# MS20_Filter_clone.net
KiCad netlist of a schematic drawn in EAGLE
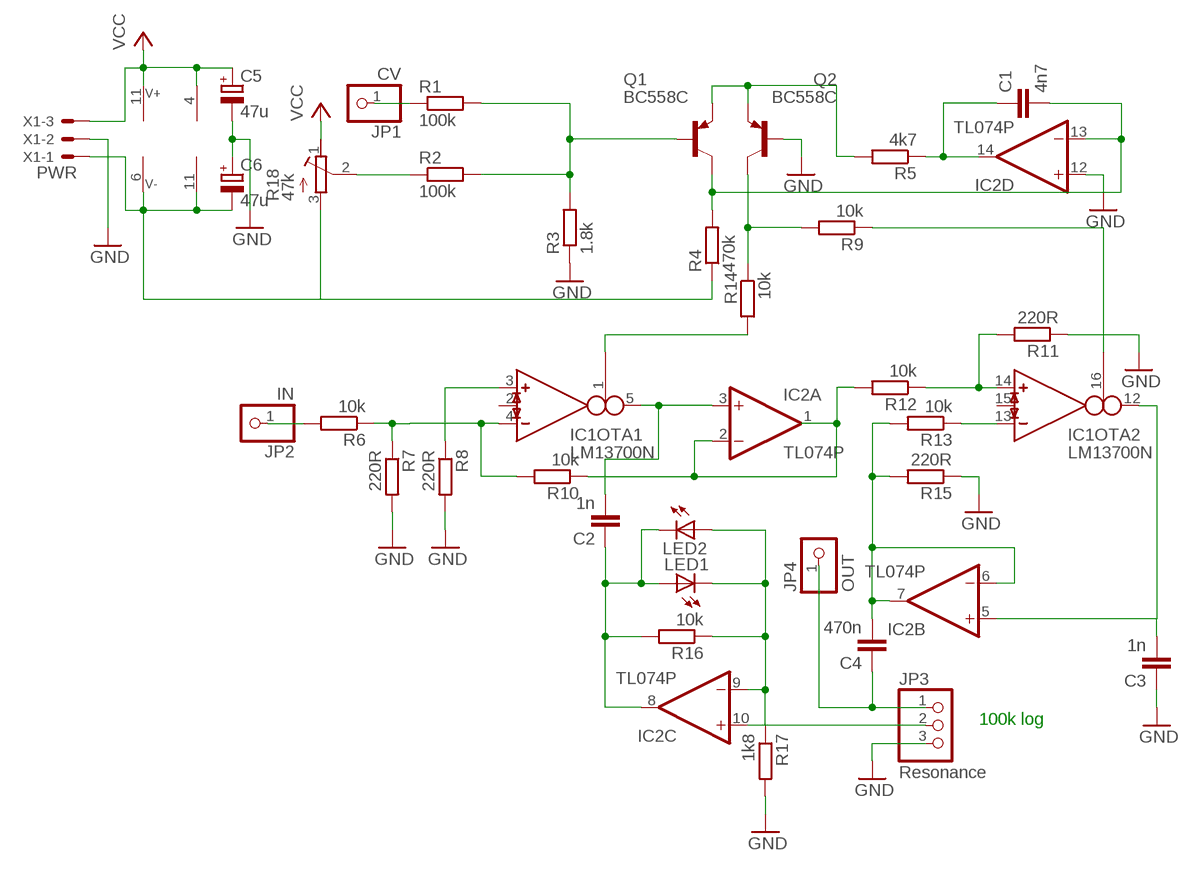
[diagram p0: schematic, sheet 1]

(export (version "E")
  (design (tool "Eeschema 10.0.6"))
  (components
    (comp (ref "C1")
      (value "4n7")
      (footprint "eagle-import:C050-024X044")
      (libsource (lib "eagle-import") (part "C-EU050-024X044"))
    )
    (comp (ref "C2")
      (value "1n")
      (footprint "eagle-import:C050-024X044")
      (libsource (lib "eagle-import") (part "C-EU050-024X044"))
    )
    (comp (ref "C3")
      (value "1n")
      (footprint "eagle-import:C050-024X044")
      (libsource (lib "eagle-import") (part "C-EU050-024X044"))
    )
    (comp (ref "C4")
      (value "470n")
      (footprint "eagle-import:C050-024X044")
      (libsource (lib "eagle-import") (part "C-EU050-024X044"))
    )
    (comp (ref "C5")
      (value "47u")
      (footprint "eagle-import:E2,5-6")
      (libsource (lib "eagle-import") (part "CPOL-EUE2.5-6"))
    )
    (comp (ref "C6")
      (value "47u")
      (footprint "eagle-import:E2,5-6")
      (libsource (lib "eagle-import") (part "CPOL-EUE2.5-6"))
    )
    (comp (ref "IC1")
      (value "LM13700N")
      (footprint "eagle-import:DIL16")
      (libsource (lib "eagle-import") (part "LM13700N"))
    )
    (comp (ref "IC2")
      (value "TL074P")
      (footprint "eagle-import:DIL14")
      (libsource (lib "eagle-import") (part "TL074P"))
    )
    (comp (ref "JP1")
      (value "CV")
      (footprint "eagle-import:1X01")
      (libsource (lib "eagle-import") (part "PINHD-1X1"))
    )
    (comp (ref "JP2")
      (value "IN")
      (footprint "eagle-import:1X01")
      (libsource (lib "eagle-import") (part "PINHD-1X1"))
    )
    (comp (ref "JP3")
      (value "Resonance")
      (footprint "eagle-import:1X03-CLEANBIG")
      (libsource (lib "eagle-import") (part "PINHD-1X3CB"))
    )
    (comp (ref "JP4")
      (value "OUT")
      (footprint "eagle-import:1X01")
      (libsource (lib "eagle-import") (part "PINHD-1X1"))
    )
    (comp (ref "LED1")
      (value "LED5MM")
      (footprint "eagle-import:LED5MM")
      (libsource (lib "eagle-import") (part "LED5MM"))
    )
    (comp (ref "LED2")
      (value "LED5MM")
      (footprint "eagle-import:LED5MM")
      (libsource (lib "eagle-import") (part "LED5MM"))
    )
    (comp (ref "Q1")
      (value "BC558C")
      (footprint "eagle-import:TO92-EBC")
      (libsource (lib "eagle-import") (part "BC558C"))
    )
    (comp (ref "Q2")
      (value "BC558C")
      (footprint "eagle-import:TO92-EBC")
      (libsource (lib "eagle-import") (part "BC558C"))
    )
    (comp (ref "R1")
      (value "100k")
      (footprint "eagle-import:0204_5")
      (libsource (lib "eagle-import") (part "R-EU_0204/5"))
    )
    (comp (ref "R2")
      (value "100k")
      (footprint "eagle-import:0204_7")
      (libsource (lib "eagle-import") (part "R-EU_0204/7"))
    )
    (comp (ref "R3")
      (value "1.8k")
      (footprint "eagle-import:0204_7")
      (libsource (lib "eagle-import") (part "R-EU_0204/7"))
    )
    (comp (ref "R4")
      (value "470k")
      (footprint "eagle-import:0204_7")
      (libsource (lib "eagle-import") (part "R-EU_0204/7"))
    )
    (comp (ref "R5")
      (value "4k7")
      (footprint "eagle-import:0204V")
      (libsource (lib "eagle-import") (part "R-EU_0204/2V"))
    )
    (comp (ref "R6")
      (value "10k")
      (footprint "eagle-import:0204_7")
      (libsource (lib "eagle-import") (part "R-EU_0204/7"))
    )
    (comp (ref "R7")
      (value "220R")
      (footprint "eagle-import:0204_7")
      (libsource (lib "eagle-import") (part "R-EU_0204/7"))
    )
    (comp (ref "R8")
      (value "220R")
      (footprint "eagle-import:0204_7")
      (libsource (lib "eagle-import") (part "R-EU_0204/7"))
    )
    (comp (ref "R9")
      (value "10k")
      (footprint "eagle-import:0204_7")
      (libsource (lib "eagle-import") (part "R-EU_0204/7"))
    )
    (comp (ref "R10")
      (value "10k")
      (footprint "eagle-import:0204_5")
      (libsource (lib "eagle-import") (part "R-EU_0204/5"))
    )
    (comp (ref "R11")
      (value "220R")
      (footprint "eagle-import:0204_5")
      (libsource (lib "eagle-import") (part "R-EU_0204/5"))
    )
    (comp (ref "R12")
      (value "10k")
      (footprint "eagle-import:0204_7")
      (libsource (lib "eagle-import") (part "R-EU_0204/7"))
    )
    (comp (ref "R13")
      (value "10k")
      (footprint "eagle-import:0204_5")
      (libsource (lib "eagle-import") (part "R-EU_0204/5"))
    )
    (comp (ref "R14")
      (value "10k")
      (footprint "eagle-import:0204V")
      (libsource (lib "eagle-import") (part "R-EU_0204/2V"))
    )
    (comp (ref "R15")
      (value "220R")
      (footprint "eagle-import:0204V")
      (libsource (lib "eagle-import") (part "R-EU_0204/2V"))
    )
    (comp (ref "R16")
      (value "10k")
      (footprint "eagle-import:0204V")
      (libsource (lib "eagle-import") (part "R-EU_0204/2V"))
    )
    (comp (ref "R17")
      (value "1k8")
      (footprint "eagle-import:0204V")
      (libsource (lib "eagle-import") (part "R-EU_0204/2V"))
    )
    (comp (ref "R18")
      (value "47k")
      (footprint "eagle-import:RTRIMT93YA")
      (libsource (lib "eagle-import") (part "R-TRIMMT93YA"))
    )
    (comp (ref "X1")
      (value "PWR")
      (footprint "eagle-import:JST-XH-03-PACKAGE-LONG-PAD")
      (libsource (lib "eagle-import") (part "JST-XH-03-PIN-LONG-PAD"))
    )
  )
  (nets
    (net (code "1") (name "GND") (class "Default")
      (node (ref "C3") (pin "1") (pinfunction "1_1") (pintype "passive"))
      (node (ref "C5") (pin "-") (pinfunction "-_-") (pintype "passive"))
      (node (ref "C6") (pin "+") (pinfunction "+_+") (pintype "passive"))
      (node (ref "IC2") (pin "12") (pinfunction "+IN_12") (pintype "input"))
      (node (ref "JP3") (pin "3") (pinfunction "3_3") (pintype "passive"))
      (node (ref "Q2") (pin "B") (pinfunction "B_B") (pintype "passive"))
      (node (ref "R11") (pin "1") (pinfunction "1_1") (pintype "passive"))
      (node (ref "R15") (pin "1") (pinfunction "1_1") (pintype "passive"))
      (node (ref "R17") (pin "2") (pinfunction "2_2") (pintype "passive"))
      (node (ref "R3") (pin "1") (pinfunction "1_1") (pintype "passive"))
      (node (ref "R7") (pin "2") (pinfunction "2_2") (pintype "passive"))
      (node (ref "R8") (pin "2") (pinfunction "2_2") (pintype "passive"))
      (node (ref "X1") (pin "2") (pinfunction "S_2") (pintype "passive"))
    )
    (net (code "2") (name "Net-(C4-Pad1)") (class "Default")
      (node (ref "C4") (pin "1") (pinfunction "1_1") (pintype "passive"))
      (node (ref "JP3") (pin "1") (pinfunction "1_1") (pintype "passive"))
      (node (ref "JP4") (pin "1") (pinfunction "1_1") (pintype "passive"))
    )
    (net (code "3") (name "Net-(IC1C-IN_N)") (class "Default")
      (node (ref "IC1") (pin "4") (pinfunction "IN_N_4") (pintype "input"))
      (node (ref "R10") (pin "2") (pinfunction "2_2") (pintype "passive"))
      (node (ref "R6") (pin "1") (pinfunction "1_1") (pintype "passive"))
      (node (ref "R7") (pin "1") (pinfunction "1_1") (pintype "passive"))
    )
    (net (code "4") (name "Net-(IC1C-IN_P)") (class "Default")
      (node (ref "IC1") (pin "3") (pinfunction "IN_P_3") (pintype "input"))
      (node (ref "R8") (pin "1") (pinfunction "1_1") (pintype "passive"))
    )
    (net (code "5") (name "Net-(IC1C-I_BIAS)") (class "Default")
      (node (ref "IC1") (pin "1") (pinfunction "I_BIAS_1") (pintype "input"))
      (node (ref "R14") (pin "2") (pinfunction "2_2") (pintype "passive"))
    )
    (net (code "6") (name "Net-(IC1C-OUT)") (class "Default")
      (node (ref "C2") (pin "2") (pinfunction "2_2") (pintype "passive"))
      (node (ref "IC1") (pin "5") (pinfunction "OUT_5") (pintype "output"))
      (node (ref "IC2") (pin "3") (pinfunction "+IN_3") (pintype "input"))
    )
    (net (code "7") (name "Net-(IC1D-IN_N)") (class "Default")
      (node (ref "IC1") (pin "13") (pinfunction "IN_N_13") (pintype "input"))
      (node (ref "R13") (pin "1") (pinfunction "1_1") (pintype "passive"))
    )
    (net (code "8") (name "Net-(IC1D-IN_P)") (class "Default")
      (node (ref "IC1") (pin "14") (pinfunction "IN_P_14") (pintype "input"))
      (node (ref "R11") (pin "2") (pinfunction "2_2") (pintype "passive"))
      (node (ref "R12") (pin "1") (pinfunction "1_1") (pintype "passive"))
    )
    (net (code "9") (name "Net-(IC1D-I_BIAS)") (class "Default")
      (node (ref "IC1") (pin "16") (pinfunction "I_BIAS_16") (pintype "input"))
      (node (ref "R9") (pin "1") (pinfunction "1_1") (pintype "passive"))
    )
    (net (code "10") (name "Net-(IC1D-OUT)") (class "Default")
      (node (ref "C3") (pin "2") (pinfunction "2_2") (pintype "passive"))
      (node (ref "IC1") (pin "12") (pinfunction "OUT_12") (pintype "output"))
      (node (ref "IC2") (pin "5") (pinfunction "+IN_5") (pintype "input"))
    )
    (net (code "11") (name "Net-(IC1E-V-)") (class "Default")
      (node (ref "C6") (pin "-") (pinfunction "-_-") (pintype "passive"))
      (node (ref "IC1") (pin "6") (pinfunction "V-_6") (pintype "power_in"))
      (node (ref "IC2") (pin "11") (pinfunction "V-_11") (pintype "power_in"))
      (node (ref "R18") (pin "3") (pinfunction "A_3") (pintype "passive"))
      (node (ref "R4") (pin "1") (pinfunction "1_1") (pintype "passive"))
      (node (ref "X1") (pin "1") (pinfunction "S_1") (pintype "passive"))
    )
    (net (code "12") (name "Net-(IC2A--IN)") (class "Default")
      (node (ref "IC2") (pin "2") (pinfunction "-IN_2") (pintype "input"))
      (node (ref "R10") (pin "1") (pinfunction "1_1") (pintype "passive"))
      (node (ref "R12") (pin "2") (pinfunction "2_2") (pintype "passive"))
    )
    (net (code "13") (name "Net-(IC2B--IN)") (class "Default")
      (node (ref "C4") (pin "2") (pinfunction "2_2") (pintype "passive"))
      (node (ref "IC2") (pin "6") (pinfunction "-IN_6") (pintype "input"))
      (node (ref "IC2") (pin "7") (pinfunction "OUT_7") (pintype "output"))
      (node (ref "R13") (pin "2") (pinfunction "2_2") (pintype "passive"))
      (node (ref "R15") (pin "2") (pinfunction "2_2") (pintype "passive"))
    )
    (net (code "14") (name "Net-(IC2C-+IN)") (class "Default")
      (node (ref "IC2") (pin "10") (pinfunction "+IN_10") (pintype "input"))
      (node (ref "JP3") (pin "2") (pinfunction "2_2") (pintype "passive"))
    )
    (net (code "15") (name "Net-(IC2C--IN)") (class "Default")
      (node (ref "IC2") (pin "9") (pinfunction "-IN_9") (pintype "input"))
      (node (ref "LED1") (pin "K") (pinfunction "C_K") (pintype "passive"))
      (node (ref "LED2") (pin "A") (pinfunction "A_A") (pintype "passive"))
      (node (ref "R16") (pin "1") (pinfunction "1_1") (pintype "passive"))
      (node (ref "R17") (pin "1") (pinfunction "1_1") (pintype "passive"))
    )
    (net (code "16") (name "Net-(IC2C-OUT)") (class "Default")
      (node (ref "C2") (pin "1") (pinfunction "1_1") (pintype "passive"))
      (node (ref "IC2") (pin "8") (pinfunction "OUT_8") (pintype "output"))
      (node (ref "LED1") (pin "A") (pinfunction "A_A") (pintype "passive"))
      (node (ref "LED2") (pin "K") (pinfunction "C_K") (pintype "passive"))
      (node (ref "R16") (pin "2") (pinfunction "2_2") (pintype "passive"))
    )
    (net (code "17") (name "Net-(IC2D--IN)") (class "Default")
      (node (ref "C1") (pin "2") (pinfunction "2_2") (pintype "passive"))
      (node (ref "IC2") (pin "13") (pinfunction "-IN_13") (pintype "input"))
      (node (ref "Q1") (pin "C") (pinfunction "C_C") (pintype "passive"))
      (node (ref "R4") (pin "2") (pinfunction "2_2") (pintype "passive"))
    )
    (net (code "18") (name "Net-(IC2D-OUT)") (class "Default")
      (node (ref "C1") (pin "1") (pinfunction "1_1") (pintype "passive"))
      (node (ref "IC2") (pin "14") (pinfunction "OUT_14") (pintype "output"))
      (node (ref "R5") (pin "1") (pinfunction "1_1") (pintype "passive"))
    )
    (net (code "19") (name "Net-(JP1-Pad1)") (class "Default")
      (node (ref "JP1") (pin "1") (pinfunction "1_1") (pintype "passive"))
      (node (ref "R1") (pin "1") (pinfunction "1_1") (pintype "passive"))
    )
    (net (code "20") (name "Net-(JP2-Pad1)") (class "Default")
      (node (ref "JP2") (pin "1") (pinfunction "1_1") (pintype "passive"))
      (node (ref "R6") (pin "2") (pinfunction "2_2") (pintype "passive"))
    )
    (net (code "21") (name "Net-(Q1-PadB)") (class "Default")
      (node (ref "Q1") (pin "B") (pinfunction "B_B") (pintype "passive"))
      (node (ref "R1") (pin "2") (pinfunction "2_2") (pintype "passive"))
      (node (ref "R2") (pin "2") (pinfunction "2_2") (pintype "passive"))
      (node (ref "R3") (pin "2") (pinfunction "2_2") (pintype "passive"))
    )
    (net (code "22") (name "Net-(Q1-PadE)") (class "Default")
      (node (ref "Q1") (pin "E") (pinfunction "E_E") (pintype "passive"))
      (node (ref "Q2") (pin "E") (pinfunction "E_E") (pintype "passive"))
      (node (ref "R5") (pin "2") (pinfunction "2_2") (pintype "passive"))
    )
    (net (code "23") (name "Net-(Q2-PadC)") (class "Default")
      (node (ref "Q2") (pin "C") (pinfunction "C_C") (pintype "passive"))
      (node (ref "R14") (pin "1") (pinfunction "1_1") (pintype "passive"))
      (node (ref "R9") (pin "2") (pinfunction "2_2") (pintype "passive"))
    )
    (net (code "24") (name "Net-(R18-S)") (class "Default")
      (node (ref "R18") (pin "2") (pinfunction "S_2") (pintype "passive"))
      (node (ref "R2") (pin "1") (pinfunction "1_1") (pintype "passive"))
    )
    (net (code "25") (name "VCC") (class "Default")
      (node (ref "C5") (pin "+") (pinfunction "+_+") (pintype "passive"))
      (node (ref "IC1") (pin "11") (pinfunction "V+_11") (pintype "power_in"))
      (node (ref "IC2") (pin "4") (pinfunction "V+_4") (pintype "power_in"))
      (node (ref "R18") (pin "1") (pinfunction "E_1") (pintype "passive"))
      (node (ref "X1") (pin "3") (pinfunction "S_3") (pintype "passive"))
    )
    (net (code "26") (name "unconnected-(IC1C-I_DIODE-Pad2)") (class "Default")
      (node (ref "IC1") (pin "2") (pinfunction "I_DIODE_2") (pintype "input"))
    )
    (net (code "27") (name "unconnected-(IC1D-I_DIODE-Pad15)") (class "Default")
      (node (ref "IC1") (pin "15") (pinfunction "I_DIODE_15") (pintype "input"))
    )
    (net (code "28") (name "unconnected-(IC2A-OUT-Pad1)") (class "Default")
      (node (ref "IC2") (pin "1") (pinfunction "OUT_1") (pintype "output"))
    )
  )
)
